# Nixie_Power_Suppy_v3_0_1.net
KiCad netlist of a schematic drawn in EAGLE
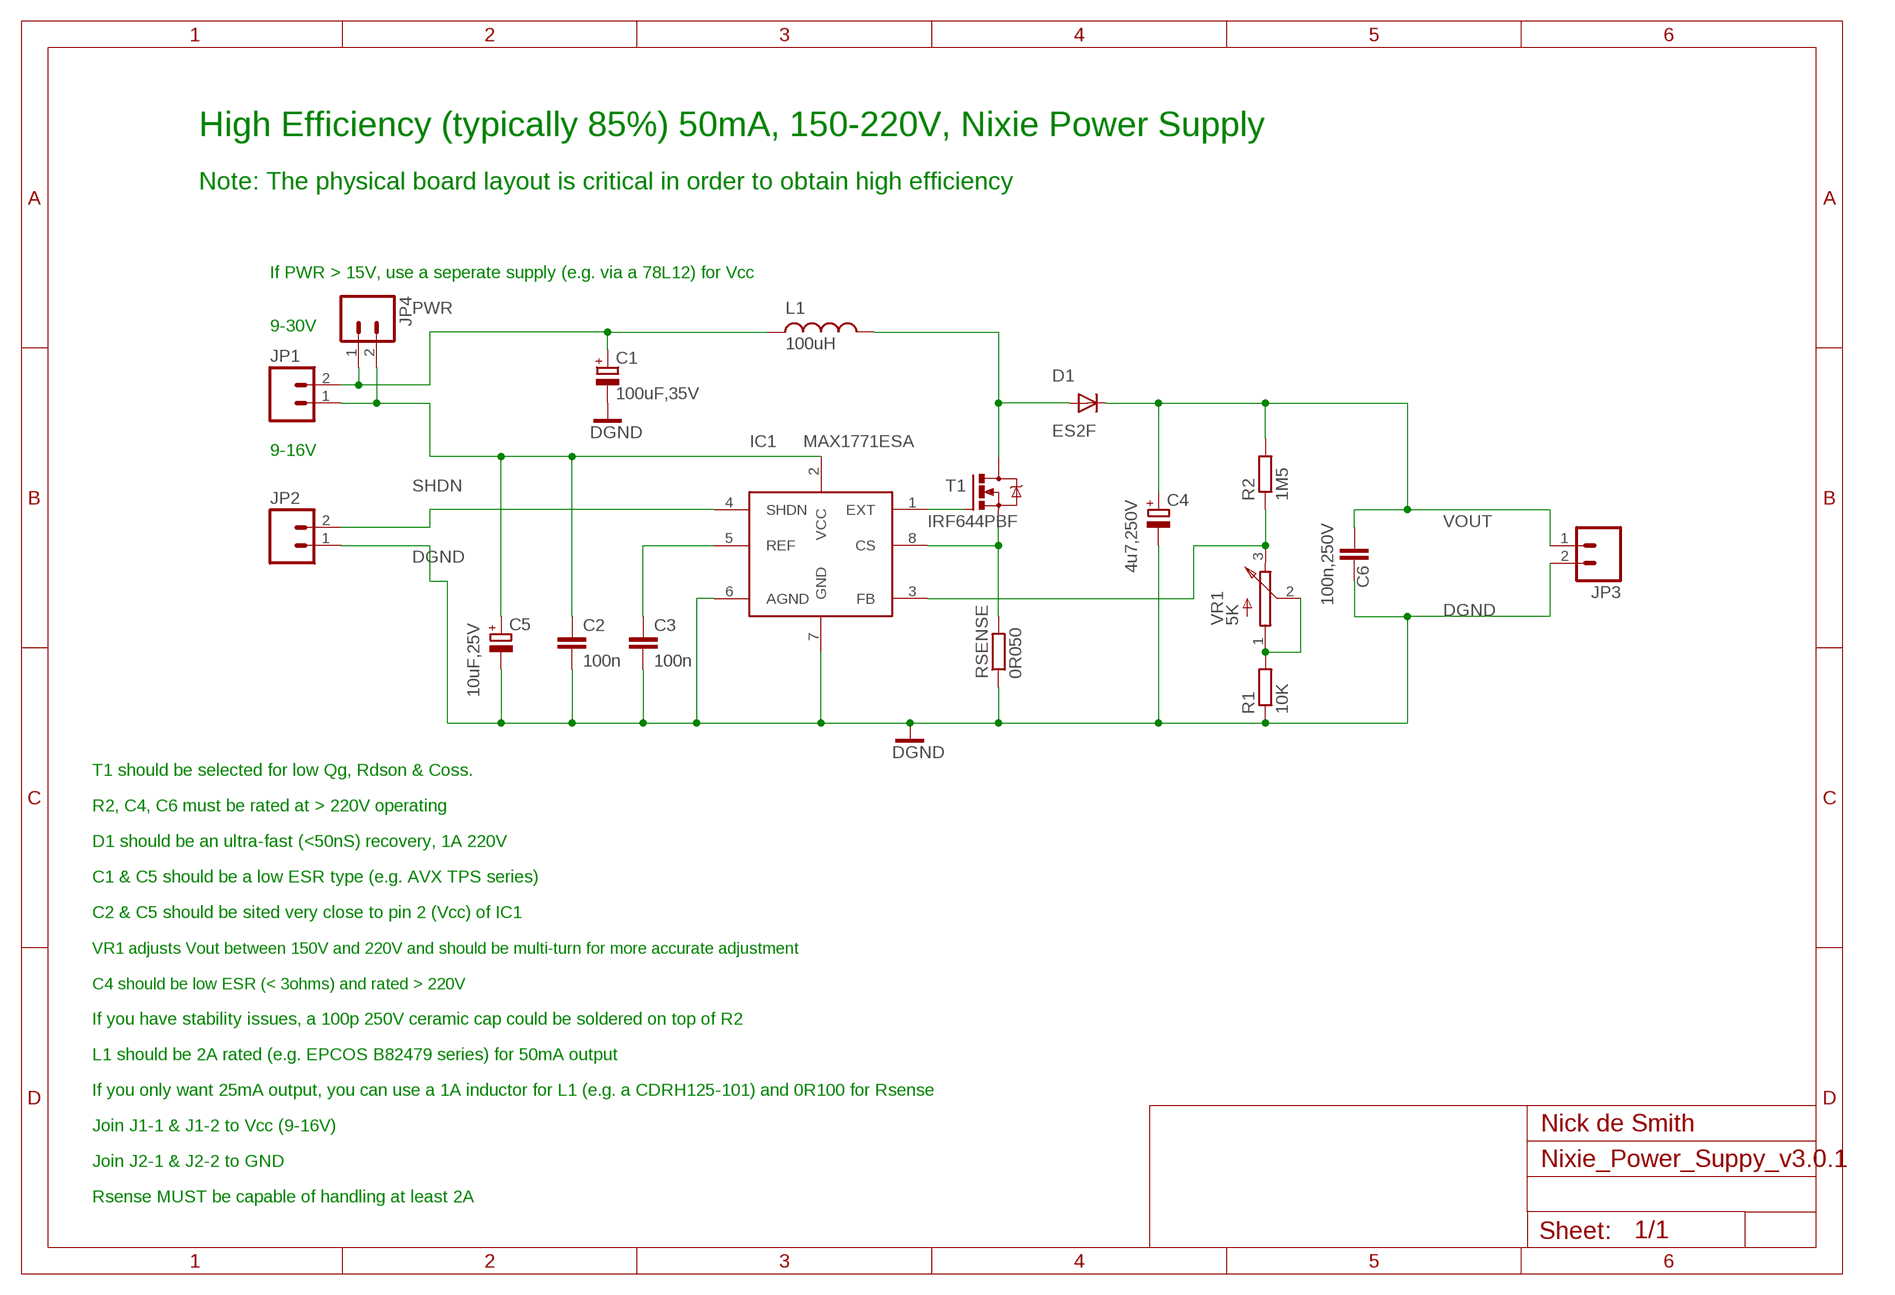
[diagram p0: schematic, sheet 1]

(export (version "E")
  (design (tool "Eeschema 10.0.6"))
  (components
    (comp (ref "C1")
      (value "100uF,35V")
      (footprint "eagle-import:C-EIA-7343")
      (libsource (lib "eagle-import") (part "C-POL-EU7343"))
    )
    (comp (ref "C2")
      (value "100n")
      (footprint "eagle-import:C0805")
      (libsource (lib "eagle-import") (part "C-EUC0805"))
    )
    (comp (ref "C3")
      (value "100n")
      (footprint "eagle-import:C0805")
      (libsource (lib "eagle-import") (part "C-EUC0805"))
    )
    (comp (ref "C4")
      (value "4u7,250V")
      (footprint "eagle-import:NICHICON-UJ-12")
      (libsource (lib "eagle-import") (part "C-POL-EU-NICHICON-UJ-12"))
    )
    (comp (ref "C5")
      (value "10uF,25V")
      (footprint "eagle-import:C-EIA-7343")
      (libsource (lib "eagle-import") (part "C-POL-EU7343"))
    )
    (comp (ref "C6")
      (value "100n,250V")
      (footprint "eagle-import:C2420")
      (libsource (lib "eagle-import") (part "C-EU-2420"))
    )
    (comp (ref "D1")
      (value "ES2F")
      (footprint "eagle-import:SMC")
      (libsource (lib "eagle-import") (part "DIODE-SMC"))
    )
    (comp (ref "IC1")
      (value "MAX1771ESA")
      (footprint "eagle-import:SO-8")
      (libsource (lib "eagle-import") (part "MAX1771ESA"))
    )
    (comp (ref "JP1")
      (value "M02PTH")
      (footprint "eagle-import:1X02")
      (libsource (lib "eagle-import") (part "M02PTH"))
    )
    (comp (ref "JP2")
      (value "M02PTH")
      (footprint "eagle-import:1X02")
      (libsource (lib "eagle-import") (part "M02PTH"))
    )
    (comp (ref "JP3")
      (value "M02PTH")
      (footprint "eagle-import:1X02")
      (libsource (lib "eagle-import") (part "M02PTH"))
    )
    (comp (ref "JP4")
      (value "M02PTH")
      (footprint "eagle-import:1X02")
      (libsource (lib "eagle-import") (part "M02PTH"))
    )
    (comp (ref "L1")
      (value "100uH")
      (footprint "eagle-import:L-B82479")
      (libsource (lib "eagle-import") (part "L-SMT-POWER-B82479"))
    )
    (comp (ref "R1")
      (value "10K")
      (footprint "eagle-import:R0805")
      (libsource (lib "eagle-import") (part "R-EU_R0805"))
    )
    (comp (ref "R2")
      (value "1M5")
      (footprint "eagle-import:R2512")
      (libsource (lib "eagle-import") (part "R-EU_R2512"))
    )
    (comp (ref "RSENSE")
      (value "0R050")
      (footprint "eagle-import:R2010")
      (libsource (lib "eagle-import") (part "R-EU_R2010"))
    )
    (comp (ref "T1")
      (value "IRF644PBF")
      (footprint "eagle-import:TO220BV")
      (libsource (lib "eagle-import") (part "IRF740"))
    )
    (comp (ref "VR1")
      (value "5K")
      (footprint "eagle-import:BOURNS-3214W")
      (libsource (lib "eagle-import") (part "TRIMPOT-3214W"))
    )
  )
  (nets
    (net (code "1") (name "/PWR") (class "Default")
      (node (ref "C1") (pin "+") (pinfunction "+_+") (pintype "passive"))
      (node (ref "JP1") (pin "2") (pinfunction "2_2") (pintype "passive"))
      (node (ref "JP4") (pin "1") (pinfunction "1_1") (pintype "passive"))
      (node (ref "L1") (pin "P$1") (pinfunction "1_P$1") (pintype "passive"))
    )
    (net (code "2") (name "/SHDN") (class "Default")
      (node (ref "IC1") (pin "4") (pinfunction "SHDN_4") (pintype "input"))
      (node (ref "JP2") (pin "2") (pinfunction "2_2") (pintype "passive"))
    )
    (net (code "3") (name "/VOUT") (class "Default")
      (node (ref "C4") (pin "2") (pinfunction "+_2") (pintype "passive"))
      (node (ref "C6") (pin "P$1") (pinfunction "1_P$1") (pintype "passive"))
      (node (ref "D1") (pin "C") (pinfunction "C_C") (pintype "passive"))
      (node (ref "JP3") (pin "1") (pinfunction "1_1") (pintype "passive"))
      (node (ref "R2") (pin "2") (pinfunction "2_2") (pintype "passive"))
    )
    (net (code "4") (name "DGND") (class "Default")
      (node (ref "C1") (pin "-") (pinfunction "-_-") (pintype "passive"))
      (node (ref "C2") (pin "2") (pinfunction "2_2") (pintype "passive"))
      (node (ref "C3") (pin "2") (pinfunction "2_2") (pintype "passive"))
      (node (ref "C4") (pin "1") (pinfunction "-_1") (pintype "passive"))
      (node (ref "C5") (pin "-") (pinfunction "-_-") (pintype "passive"))
      (node (ref "C6") (pin "P$2") (pinfunction "2_P$2") (pintype "passive"))
      (node (ref "IC1") (pin "6") (pinfunction "AGND_6") (pintype "input"))
      (node (ref "IC1") (pin "7") (pinfunction "GND_7") (pintype "input"))
      (node (ref "JP2") (pin "1") (pinfunction "1_1") (pintype "passive"))
      (node (ref "JP3") (pin "2") (pinfunction "2_2") (pintype "passive"))
      (node (ref "R1") (pin "1") (pinfunction "1_1") (pintype "passive"))
      (node (ref "RSENSE") (pin "1") (pinfunction "1_1") (pintype "passive"))
    )
    (net (code "5") (name "Net-(IC1-CS)") (class "Default")
      (node (ref "IC1") (pin "8") (pinfunction "CS_8") (pintype "input"))
      (node (ref "RSENSE") (pin "2") (pinfunction "2_2") (pintype "passive"))
      (node (ref "T1") (pin "S") (pinfunction "S_S") (pintype "passive"))
    )
    (net (code "6") (name "Net-(IC1-EXT)") (class "Default")
      (node (ref "IC1") (pin "1") (pinfunction "EXT_1") (pintype "output"))
      (node (ref "T1") (pin "G") (pinfunction "G_G") (pintype "passive"))
    )
    (net (code "7") (name "Net-(IC1-FB)") (class "Default")
      (node (ref "IC1") (pin "3") (pinfunction "FB_3") (pintype "input"))
      (node (ref "R2") (pin "1") (pinfunction "1_1") (pintype "passive"))
      (node (ref "VR1") (pin "3") (pinfunction "B_3") (pintype "passive"))
    )
    (net (code "8") (name "Net-(IC1-REF)") (class "Default")
      (node (ref "C3") (pin "1") (pinfunction "1_1") (pintype "passive"))
      (node (ref "IC1") (pin "5") (pinfunction "REF_5") (pintype "input"))
    )
    (net (code "9") (name "Net-(IC1-VCC)") (class "Default")
      (node (ref "C2") (pin "1") (pinfunction "1_1") (pintype "passive"))
      (node (ref "C5") (pin "+") (pinfunction "+_+") (pintype "passive"))
      (node (ref "IC1") (pin "2") (pinfunction "VCC_2") (pintype "input"))
      (node (ref "JP1") (pin "1") (pinfunction "1_1") (pintype "passive"))
      (node (ref "JP4") (pin "2") (pinfunction "2_2") (pintype "passive"))
    )
    (net (code "10") (name "Net-(L1-2)") (class "Default")
      (node (ref "D1") (pin "A") (pinfunction "A_A") (pintype "passive"))
      (node (ref "L1") (pin "P$2") (pinfunction "2_P$2") (pintype "passive"))
      (node (ref "T1") (pin "D") (pinfunction "D_D") (pintype "passive"))
    )
    (net (code "11") (name "Net-(VR1-A)") (class "Default")
      (node (ref "R1") (pin "2") (pinfunction "2_2") (pintype "passive"))
      (node (ref "VR1") (pin "1") (pinfunction "A_1") (pintype "passive"))
      (node (ref "VR1") (pin "2") (pinfunction "W_2") (pintype "passive"))
    )
  )
)
